# Base_Station.net
KiCad netlist of a schematic drawn in EAGLE
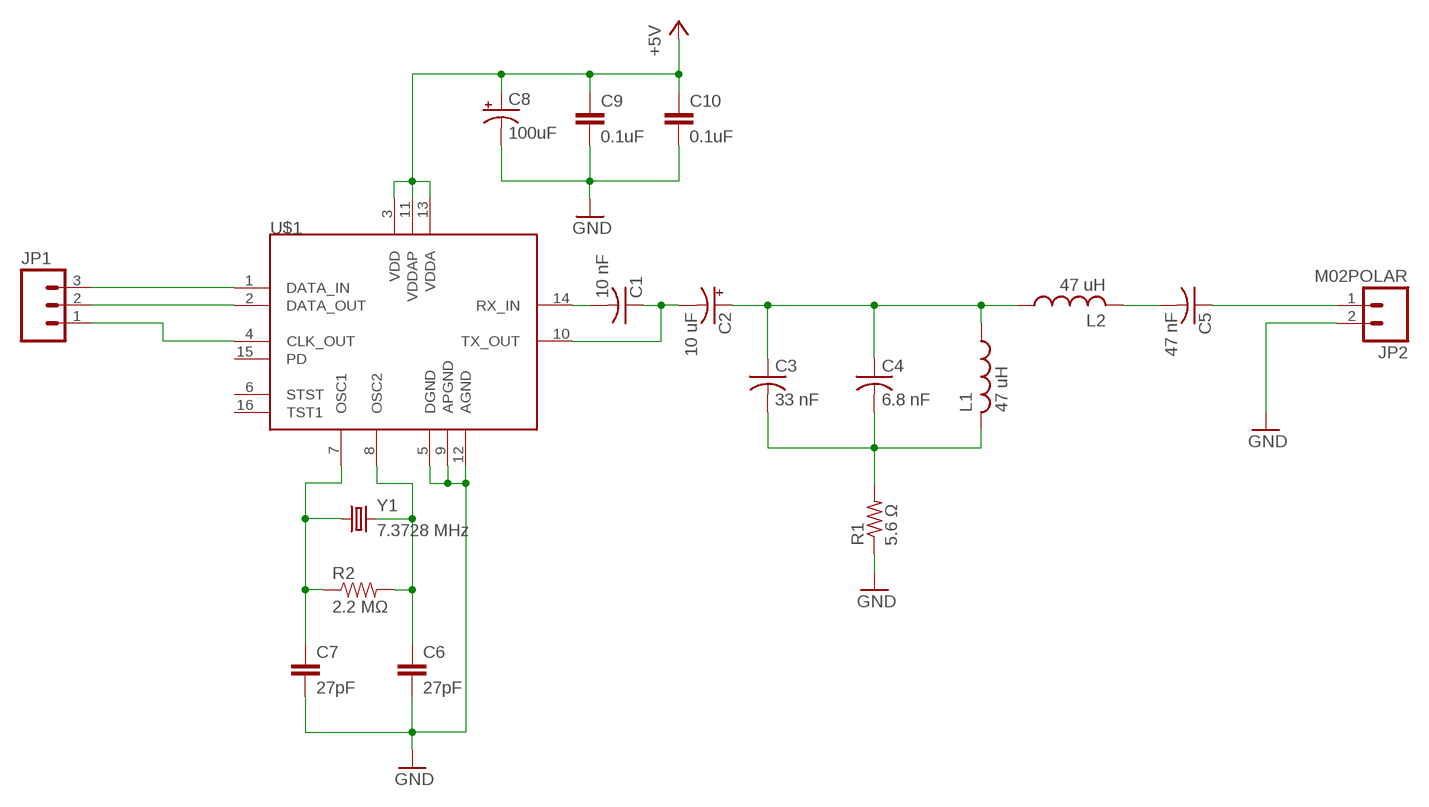
[diagram p0: schematic, sheet 1]

(export (version "E")
  (design (tool "Eeschema 10.0.6"))
  (components
    (comp (ref "C1")
      (value "10 nF")
      (footprint "eagle-import:C025-030X050")
      (libsource (lib "eagle-import") (part "C-US025-030X050"))
    )
    (comp (ref "C2")
      (value "10 uF")
      (footprint "eagle-import:E2-5")
      (libsource (lib "eagle-import") (part "CPOL-USE2-5"))
    )
    (comp (ref "C3")
      (value "33 nF")
      (footprint "eagle-import:C050-050X075")
      (libsource (lib "eagle-import") (part "C-US050-050X075"))
    )
    (comp (ref "C4")
      (value "6.8 nF")
      (footprint "eagle-import:C102-043X133")
      (libsource (lib "eagle-import") (part "C-US102-043X133"))
    )
    (comp (ref "C5")
      (value "47 nF")
      (footprint "eagle-import:C075-063X106")
      (libsource (lib "eagle-import") (part "C-US075-063X106"))
    )
    (comp (ref "C6")
      (value "27pF")
      (footprint "eagle-import:CAP-PTH-5MM")
      (libsource (lib "eagle-import") (part "SparkFun-Passives_CAPPTH1"))
    )
    (comp (ref "C7")
      (value "27pF")
      (footprint "eagle-import:CAP-PTH-5MM")
      (libsource (lib "eagle-import") (part "SparkFun-Passives_CAPPTH1"))
    )
    (comp (ref "C8")
      (value "100uF")
      (footprint "eagle-import:CPOL-RADIAL-100UF-25V")
      (libsource (lib "eagle-import") (part "CAP_POLPTH1"))
    )
    (comp (ref "C9")
      (value "0.1uF")
      (footprint "eagle-import:CAP-PTH-5MM")
      (libsource (lib "eagle-import") (part "CAPPTH1"))
    )
    (comp (ref "C10")
      (value "0.1uF")
      (footprint "eagle-import:CAP-PTH-5MM")
      (libsource (lib "eagle-import") (part "CAPPTH1"))
    )
    (comp (ref "JP1")
      (value "M03POLAR")
      (footprint "eagle-import:MOLEX-1X3")
      (libsource (lib "eagle-import") (part "M03POLAR"))
    )
    (comp (ref "JP2")
      (value "M02POLAR")
      (footprint "eagle-import:MOLEX-1X2")
      (libsource (lib "eagle-import") (part "M02POLAR"))
    )
    (comp (ref "L1")
      (value "47 uH")
      (footprint "eagle-import:0204_7")
      (libsource (lib "eagle-import") (part "L-US0204/7"))
    )
    (comp (ref "L2")
      (value "47 uH")
      (footprint "eagle-import:0207_10")
      (libsource (lib "eagle-import") (part "L-US0207/10"))
    )
    (comp (ref "R1")
      (value "5.6 Ω")
      (footprint "eagle-import:0207_7")
      (libsource (lib "eagle-import") (part "R-US_0207/7"))
    )
    (comp (ref "R2")
      (value "2.2 MΩ")
      (footprint "eagle-import:AXIAL-0.4")
      (libsource (lib "eagle-import") (part "RESISTORPTH-1/4W"))
    )
    (comp (ref "U$1")
      (value "TDA5052AT")
      (footprint "eagle-import:SO16L")
      (libsource (lib "eagle-import") (part "TDA5052AT"))
    )
    (comp (ref "Y1")
      (value "7.3728 MHz")
      (footprint "eagle-import:HC49US")
      (libsource (lib "eagle-import") (part "CRYSTALHC49US"))
    )
  )
  (nets
    (net (code "1") (name "+5V") (class "Default")
      (node (ref "C10") (pin "1") (pinfunction "1_1") (pintype "passive"))
      (node (ref "C8") (pin "1") (pinfunction "+_1") (pintype "passive"))
      (node (ref "C9") (pin "1") (pinfunction "1_1") (pintype "passive"))
      (node (ref "U$1") (pin "11") (pinfunction "VDDAP_11") (pintype "bidirectional"))
      (node (ref "U$1") (pin "13") (pinfunction "VDDA_13") (pintype "bidirectional"))
      (node (ref "U$1") (pin "3") (pinfunction "VDD_3") (pintype "bidirectional"))
    )
    (net (code "2") (name "GND") (class "Default")
      (node (ref "C10") (pin "2") (pinfunction "2_2") (pintype "passive"))
      (node (ref "C6") (pin "2") (pinfunction "2_2") (pintype "passive"))
      (node (ref "C7") (pin "2") (pinfunction "2_2") (pintype "passive"))
      (node (ref "C8") (pin "2") (pinfunction "-_2") (pintype "passive"))
      (node (ref "C9") (pin "2") (pinfunction "2_2") (pintype "passive"))
      (node (ref "JP2") (pin "2") (pinfunction "2_2") (pintype "passive"))
      (node (ref "R1") (pin "1") (pinfunction "1_1") (pintype "passive"))
      (node (ref "U$1") (pin "12") (pinfunction "AGND_12") (pintype "bidirectional"))
      (node (ref "U$1") (pin "5") (pinfunction "DGND_5") (pintype "bidirectional"))
      (node (ref "U$1") (pin "9") (pinfunction "APGND_9") (pintype "bidirectional"))
    )
    (net (code "3") (name "Net-(C2-Pad+)") (class "Default")
      (node (ref "C2") (pin "+") (pinfunction "+_+") (pintype "passive"))
      (node (ref "C3") (pin "1") (pinfunction "1_1") (pintype "passive"))
      (node (ref "C4") (pin "1") (pinfunction "1_1") (pintype "passive"))
      (node (ref "L1") (pin "1") (pinfunction "1_1") (pintype "passive"))
      (node (ref "L2") (pin "1") (pinfunction "1_1") (pintype "passive"))
    )
    (net (code "4") (name "Net-(C3-Pad2)") (class "Default")
      (node (ref "C3") (pin "2") (pinfunction "2_2") (pintype "passive"))
      (node (ref "C4") (pin "2") (pinfunction "2_2") (pintype "passive"))
      (node (ref "L1") (pin "2") (pinfunction "2_2") (pintype "passive"))
      (node (ref "R1") (pin "2") (pinfunction "2_2") (pintype "passive"))
    )
    (net (code "5") (name "Net-(C5-Pad1)") (class "Default")
      (node (ref "C5") (pin "1") (pinfunction "1_1") (pintype "passive"))
      (node (ref "JP2") (pin "1") (pinfunction "1_1") (pintype "passive"))
    )
    (net (code "6") (name "Net-(C5-Pad2)") (class "Default")
      (node (ref "C5") (pin "2") (pinfunction "2_2") (pintype "passive"))
      (node (ref "L2") (pin "2") (pinfunction "2_2") (pintype "passive"))
    )
    (net (code "7") (name "Net-(R2-1)") (class "Default")
      (node (ref "C7") (pin "1") (pinfunction "1_1") (pintype "passive"))
      (node (ref "R2") (pin "P$1") (pinfunction "1_P$1") (pintype "passive"))
      (node (ref "U$1") (pin "7") (pinfunction "OSC1_7") (pintype "bidirectional"))
      (node (ref "Y1") (pin "1") (pinfunction "1_1") (pintype "passive"))
    )
    (net (code "8") (name "Net-(R2-2)") (class "Default")
      (node (ref "C6") (pin "1") (pinfunction "1_1") (pintype "passive"))
      (node (ref "R2") (pin "P$2") (pinfunction "2_P$2") (pintype "passive"))
      (node (ref "U$1") (pin "8") (pinfunction "OSC2_8") (pintype "bidirectional"))
      (node (ref "Y1") (pin "2") (pinfunction "2_2") (pintype "passive"))
    )
    (net (code "9") (name "Net-(U$1-CLK_OUT)") (class "Default")
      (node (ref "JP1") (pin "1") (pinfunction "1_1") (pintype "passive"))
      (node (ref "U$1") (pin "4") (pinfunction "CLK_OUT_4") (pintype "bidirectional"))
    )
    (net (code "10") (name "Net-(U$1-DATA_IN)") (class "Default")
      (node (ref "JP1") (pin "3") (pinfunction "3_3") (pintype "passive"))
      (node (ref "U$1") (pin "1") (pinfunction "DATA_IN_1") (pintype "bidirectional"))
    )
    (net (code "11") (name "Net-(U$1-DATA_OUT)") (class "Default")
      (node (ref "JP1") (pin "2") (pinfunction "2_2") (pintype "passive"))
      (node (ref "U$1") (pin "2") (pinfunction "DATA_OUT_2") (pintype "bidirectional"))
    )
    (net (code "12") (name "Net-(U$1-RX_IN)") (class "Default")
      (node (ref "C1") (pin "2") (pinfunction "2_2") (pintype "passive"))
      (node (ref "U$1") (pin "14") (pinfunction "RX_IN_14") (pintype "bidirectional"))
    )
    (net (code "13") (name "Net-(U$1-TX_OUT)") (class "Default")
      (node (ref "C1") (pin "1") (pinfunction "1_1") (pintype "passive"))
      (node (ref "C2") (pin "-") (pinfunction "-_-") (pintype "passive"))
      (node (ref "U$1") (pin "10") (pinfunction "TX_OUT_10") (pintype "bidirectional"))
    )
    (net (code "14") (name "unconnected-(U$1-PD-Pad15)") (class "Default")
      (node (ref "U$1") (pin "15") (pinfunction "PD_15") (pintype "bidirectional"))
    )
    (net (code "15") (name "unconnected-(U$1-STST-Pad6)") (class "Default")
      (node (ref "U$1") (pin "6") (pinfunction "STST_6") (pintype "bidirectional"))
    )
    (net (code "16") (name "unconnected-(U$1-TST1-Pad16)") (class "Default")
      (node (ref "U$1") (pin "16") (pinfunction "TST1_16") (pintype "bidirectional"))
    )
  )
)
